# wheel.net
KiCad netlist of a schematic drawn in EAGLE
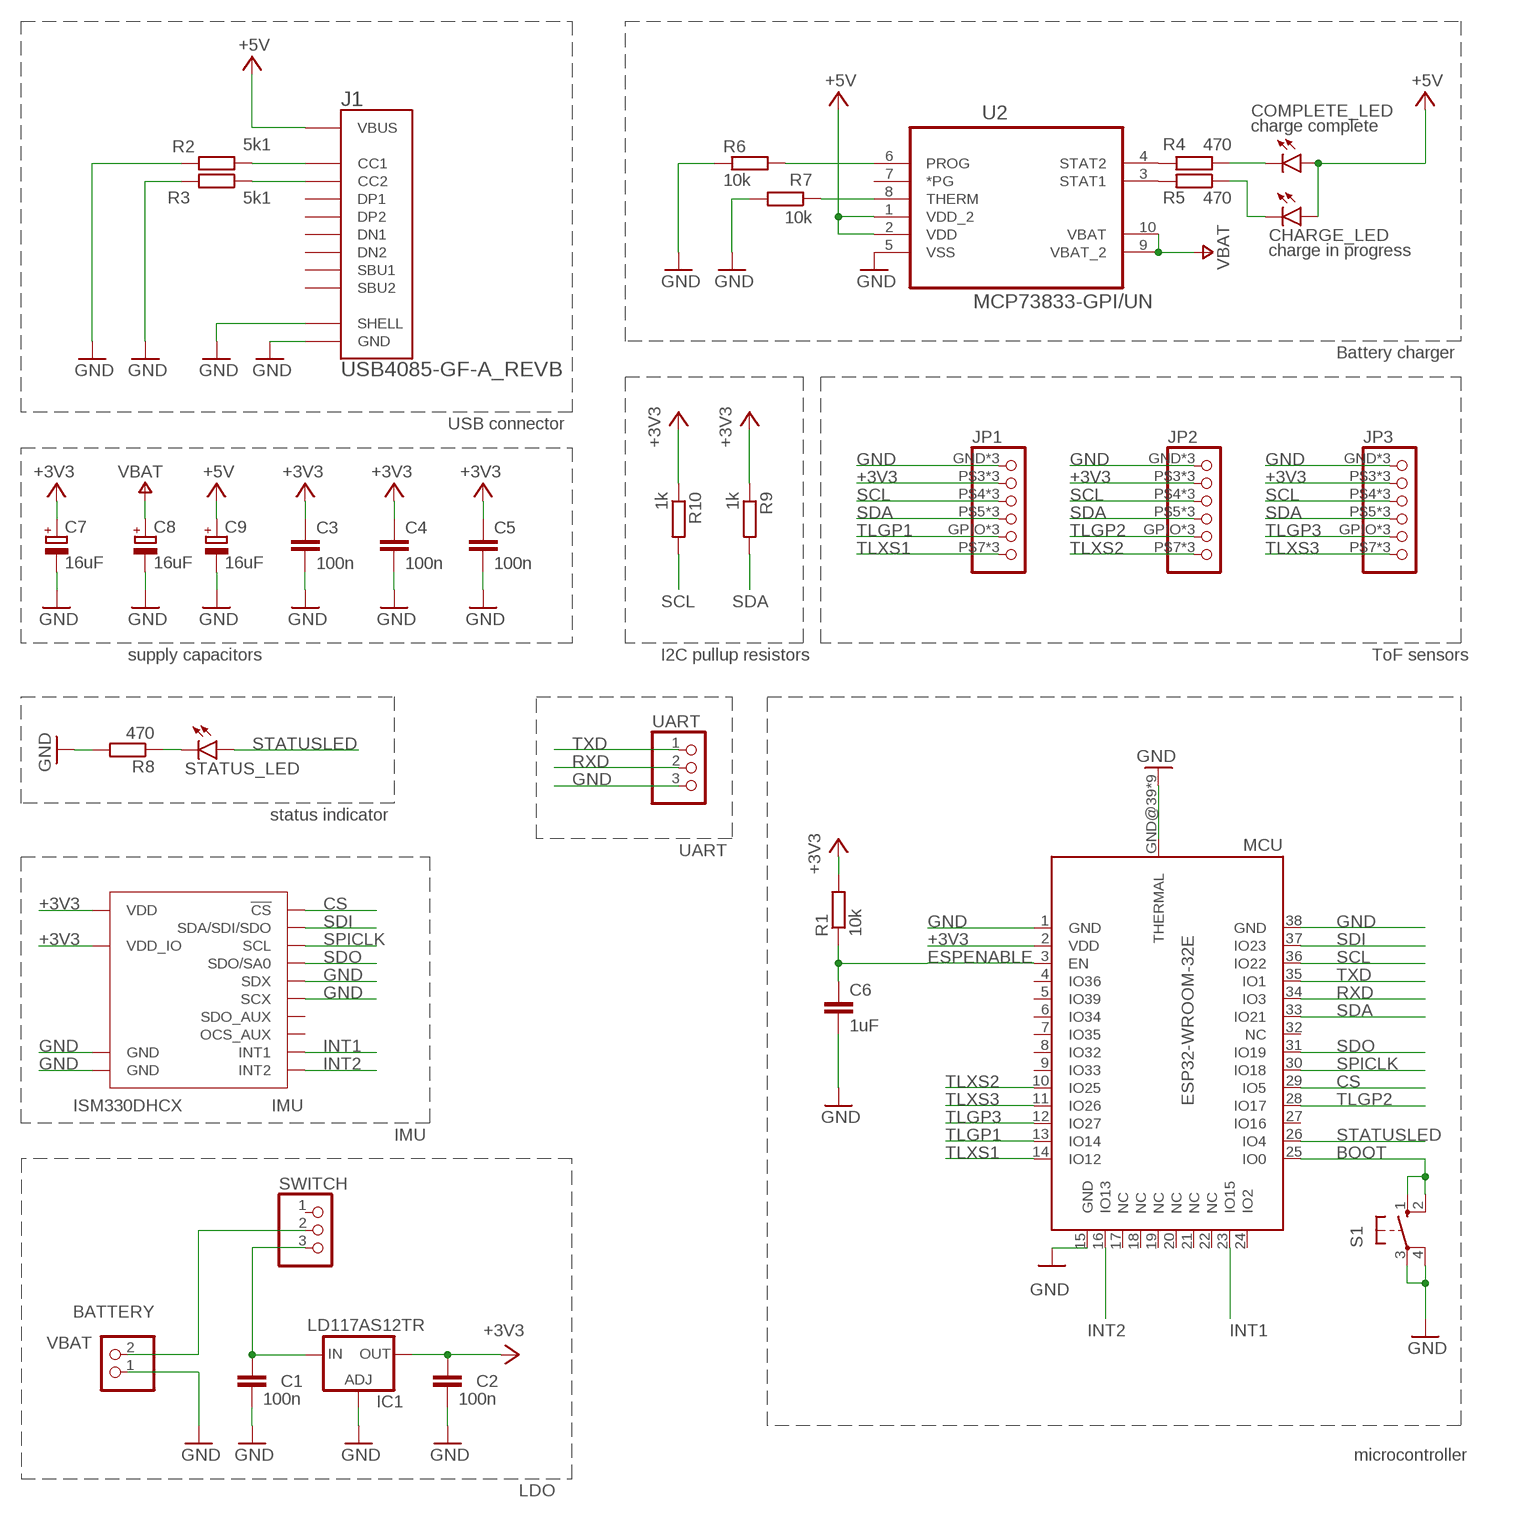
[diagram p0: schematic, sheet 1]

(export (version "E")
  (design (tool "Eeschema 10.0.6"))
  (components
    (comp (ref "BATTERY")
      (value "PINHD-1X2")
      (footprint "eagle-import:1X02")
      (libsource (lib "eagle-import") (part "PINHD-1X2"))
    )
    (comp (ref "C1")
      (value "100n")
      (footprint "eagle-import:C1206")
      (libsource (lib "eagle-import") (part "C-EUC1206"))
    )
    (comp (ref "C2")
      (value "100n")
      (footprint "eagle-import:C1206")
      (libsource (lib "eagle-import") (part "C-EUC1206"))
    )
    (comp (ref "C3")
      (value "100n")
      (footprint "eagle-import:C1206")
      (libsource (lib "eagle-import") (part "C-EUC1206"))
    )
    (comp (ref "C4")
      (value "100n")
      (footprint "eagle-import:C1206")
      (libsource (lib "eagle-import") (part "C-EUC1206"))
    )
    (comp (ref "C5")
      (value "100n")
      (footprint "eagle-import:C1206")
      (libsource (lib "eagle-import") (part "C-EUC1206"))
    )
    (comp (ref "C6")
      (value "1uF")
      (footprint "eagle-import:C1206")
      (libsource (lib "eagle-import") (part "C-EUC1206"))
    )
    (comp (ref "C7")
      (value "16uF")
      (footprint "eagle-import:E2,5-7")
      (libsource (lib "eagle-import") (part "CPOL-EUE2.5-7"))
    )
    (comp (ref "C8")
      (value "16uF")
      (footprint "eagle-import:E2,5-7")
      (libsource (lib "eagle-import") (part "CPOL-EUE2.5-7"))
    )
    (comp (ref "C9")
      (value "16uF")
      (footprint "eagle-import:E2,5-7")
      (libsource (lib "eagle-import") (part "CPOL-EUE2.5-7"))
    )
    (comp (ref "CHARGE_LED")
      (value "charge in progress")
      (footprint "eagle-import:CHIPLED_1206")
      (libsource (lib "eagle-import") (part "LEDCHIPLED_1206"))
    )
    (comp (ref "COMPLETE_LED")
      (value "charge complete")
      (footprint "eagle-import:CHIPLED_1206")
      (libsource (lib "eagle-import") (part "LEDCHIPLED_1206"))
    )
    (comp (ref "IC1")
      (value "LD117AS12TR")
      (footprint "eagle-import:SOT223")
      (libsource (lib "eagle-import") (part "LD117A?S12TR"))
    )
    (comp (ref "IMU")
      (value "ISM330DHCX")
      (footprint "eagle-import:LGA-14L")
      (libsource (lib "eagle-import") (part "ISM330DHCX"))
    )
    (comp (ref "J1")
      (value "USB4085-GF-A_REVB")
      (footprint "eagle-import:GCT_USB4085-GF-A_REVB")
      (fields (field (name "MF") "Global Connector Technology") (field (name "MP") "USB4085-GF-A"))
      (libsource (lib "eagle-import") (part "USB4085-GF-A_REVB"))
    )
    (comp (ref "JP1")
      (value "PINHD-1X6")
      (footprint "eagle-import:1X06")
      (libsource (lib "eagle-import") (part "PINHD-1X6"))
    )
    (comp (ref "JP2")
      (value "PINHD-1X6")
      (footprint "eagle-import:1X06")
      (libsource (lib "eagle-import") (part "PINHD-1X6"))
    )
    (comp (ref "JP3")
      (value "PINHD-1X6")
      (footprint "eagle-import:1X06")
      (libsource (lib "eagle-import") (part "PINHD-1X6"))
    )
    (comp (ref "MCU")
      (value "ESP32-WROOM-32E")
      (footprint "eagle-import:ESP32-WROOM-32E")
      (fields (field (name "MF") "Espressif Systems"))
      (libsource (lib "eagle-import") (part "ESP32-WROOM-32E"))
    )
    (comp (ref "R1")
      (value "10k")
      (footprint "eagle-import:R1206")
      (libsource (lib "eagle-import") (part "R-EU_R1206"))
    )
    (comp (ref "R2")
      (value "5k1")
      (footprint "eagle-import:R1206")
      (libsource (lib "eagle-import") (part "R-EU_R1206"))
    )
    (comp (ref "R3")
      (value "5k1")
      (footprint "eagle-import:R1206")
      (libsource (lib "eagle-import") (part "R-EU_R1206"))
    )
    (comp (ref "R4")
      (value "470")
      (footprint "eagle-import:R1206")
      (libsource (lib "eagle-import") (part "R-EU_R1206"))
    )
    (comp (ref "R5")
      (value "470")
      (footprint "eagle-import:R1206")
      (libsource (lib "eagle-import") (part "R-EU_R1206"))
    )
    (comp (ref "R6")
      (value "10k")
      (footprint "eagle-import:R1206")
      (libsource (lib "eagle-import") (part "R-EU_R1206"))
    )
    (comp (ref "R7")
      (value "10k")
      (footprint "eagle-import:R1206")
      (libsource (lib "eagle-import") (part "R-EU_R1206"))
    )
    (comp (ref "R8")
      (value "470")
      (footprint "eagle-import:R1206")
      (libsource (lib "eagle-import") (part "R-EU_R1206"))
    )
    (comp (ref "R9")
      (value "1k")
      (footprint "eagle-import:R1206")
      (libsource (lib "eagle-import") (part "R-EU_R1206"))
    )
    (comp (ref "R10")
      (value "1k")
      (footprint "eagle-import:R1206")
      (libsource (lib "eagle-import") (part "R-EU_R1206"))
    )
    (comp (ref "S1")
      (value "10-XX")
      (footprint "eagle-import:B3F-10XX")
      (fields (field (name "MPN") "B3F-1000"))
      (libsource (lib "eagle-import") (part "10-XX"))
    )
    (comp (ref "STATUS_LED")
      (value "status")
      (footprint "eagle-import:CHIPLED_1206")
      (libsource (lib "eagle-import") (part "LEDCHIPLED_1206"))
    )
    (comp (ref "SWITCH")
      (value "PINHD-1X3")
      (footprint "eagle-import:1X03")
      (libsource (lib "eagle-import") (part "PINHD-1X3"))
    )
    (comp (ref "U2")
      (value "MCP73833-GPI/UN")
      (footprint "eagle-import:SOP50P490X110-10N")
      (fields (field (name "MF") "Microchip"))
      (libsource (lib "eagle-import") (part "MCP73833-GPI/UN"))
    )
    (comp (ref "UART")
      (value "PINHD-1X3")
      (footprint "eagle-import:1X03")
      (libsource (lib "eagle-import") (part "PINHD-1X3"))
    )
  )
  (nets
    (net (code "1") (name "+3V3") (class "Default")
      (node (ref "C2") (pin "1") (pinfunction "1_1") (pintype "passive"))
      (node (ref "C3") (pin "1") (pinfunction "1_1") (pintype "passive"))
      (node (ref "C4") (pin "1") (pinfunction "1_1") (pintype "passive"))
      (node (ref "C5") (pin "1") (pinfunction "1_1") (pintype "passive"))
      (node (ref "C7") (pin "+") (pinfunction "+_+") (pintype "passive"))
      (node (ref "IC1") (pin "4") (pinfunction "OUT_4") (pintype "passive"))
      (node (ref "IMU") (pin "P5") (pinfunction "VDD_IO_P5") (pintype "power_in"))
      (node (ref "IMU") (pin "P8") (pinfunction "VDD_P8") (pintype "power_in"))
      (node (ref "JP1") (pin "P$3") (pinfunction "2_P$3") (pintype "passive"))
      (node (ref "JP1") (pin "P$8") (pinfunction "2_P$8") (pintype "passive"))
      (node (ref "JP1") (pin "VCC") (pinfunction "2_VCC") (pintype "passive"))
      (node (ref "JP2") (pin "P$3") (pinfunction "2_P$3") (pintype "passive"))
      (node (ref "JP2") (pin "P$8") (pinfunction "2_P$8") (pintype "passive"))
      (node (ref "JP2") (pin "VCC") (pinfunction "2_VCC") (pintype "passive"))
      (node (ref "JP3") (pin "P$3") (pinfunction "2_P$3") (pintype "passive"))
      (node (ref "JP3") (pin "P$8") (pinfunction "2_P$8") (pintype "passive"))
      (node (ref "JP3") (pin "VCC") (pinfunction "2_VCC") (pintype "passive"))
      (node (ref "MCU") (pin "2") (pinfunction "VDD_2") (pintype "bidirectional"))
      (node (ref "R1") (pin "2") (pinfunction "2_2") (pintype "passive"))
      (node (ref "R10") (pin "1") (pinfunction "1_1") (pintype "passive"))
      (node (ref "R9") (pin "1") (pinfunction "1_1") (pintype "passive"))
    )
    (net (code "2") (name "+5V") (class "Default")
      (node (ref "C9") (pin "+") (pinfunction "+_+") (pintype "passive"))
      (node (ref "CHARGE_LED") (pin "A") (pinfunction "A_A") (pintype "passive"))
      (node (ref "COMPLETE_LED") (pin "A") (pinfunction "A_A") (pintype "passive"))
      (node (ref "J1") (pin "A4") (pinfunction "VBUS_A4") (pintype "power_in"))
      (node (ref "J1") (pin "A9") (pinfunction "VBUS_A9") (pintype "power_in"))
      (node (ref "J1") (pin "B4") (pinfunction "VBUS_B4") (pintype "power_in"))
      (node (ref "J1") (pin "B9") (pinfunction "VBUS_B9") (pintype "power_in"))
      (node (ref "U2") (pin "1") (pinfunction "VDD_2_1") (pintype "power_in"))
      (node (ref "U2") (pin "2") (pinfunction "VDD_2") (pintype "power_in"))
    )
    (net (code "3") (name "/BOOT") (class "Default")
      (node (ref "MCU") (pin "25") (pinfunction "IO0_25") (pintype "bidirectional"))
      (node (ref "S1") (pin "1") (pinfunction "S_1") (pintype "passive"))
      (node (ref "S1") (pin "2") (pinfunction "S1_2") (pintype "passive"))
    )
    (net (code "4") (name "/CS") (class "Default")
      (node (ref "IMU") (pin "P12") (pinfunction "~{CS}_P12") (pintype "bidirectional"))
      (node (ref "MCU") (pin "29") (pinfunction "IO5_29") (pintype "bidirectional"))
    )
    (net (code "5") (name "/ESPENABLE") (class "Default")
      (node (ref "C6") (pin "1") (pinfunction "1_1") (pintype "passive"))
      (node (ref "MCU") (pin "3") (pinfunction "EN_3") (pintype "bidirectional"))
      (node (ref "R1") (pin "1") (pinfunction "1_1") (pintype "passive"))
    )
    (net (code "6") (name "/INT1") (class "Default")
      (node (ref "IMU") (pin "P4") (pinfunction "INT1_P4") (pintype "bidirectional"))
      (node (ref "MCU") (pin "23") (pinfunction "IO15_23") (pintype "bidirectional"))
    )
    (net (code "7") (name "/INT2") (class "Default")
      (node (ref "IMU") (pin "P9") (pinfunction "INT2_P9") (pintype "bidirectional"))
      (node (ref "MCU") (pin "16") (pinfunction "IO13_16") (pintype "bidirectional"))
    )
    (net (code "8") (name "/RXD") (class "Default")
      (node (ref "MCU") (pin "34") (pinfunction "IO3_34") (pintype "bidirectional"))
      (node (ref "UART") (pin "2") (pinfunction "2_2") (pintype "passive"))
    )
    (net (code "9") (name "/SCL") (class "Default")
      (node (ref "JP1") (pin "P$4") (pinfunction "3_P$4") (pintype "passive"))
      (node (ref "JP1") (pin "P$9") (pinfunction "3_P$9") (pintype "passive"))
      (node (ref "JP1") (pin "SCL") (pinfunction "3_SCL") (pintype "passive"))
      (node (ref "JP2") (pin "P$4") (pinfunction "3_P$4") (pintype "passive"))
      (node (ref "JP2") (pin "P$9") (pinfunction "3_P$9") (pintype "passive"))
      (node (ref "JP2") (pin "SCL") (pinfunction "3_SCL") (pintype "passive"))
      (node (ref "JP3") (pin "P$4") (pinfunction "3_P$4") (pintype "passive"))
      (node (ref "JP3") (pin "P$9") (pinfunction "3_P$9") (pintype "passive"))
      (node (ref "JP3") (pin "SCL") (pinfunction "3_SCL") (pintype "passive"))
      (node (ref "MCU") (pin "36") (pinfunction "IO22_36") (pintype "bidirectional"))
      (node (ref "R10") (pin "2") (pinfunction "2_2") (pintype "passive"))
    )
    (net (code "10") (name "/SDA") (class "Default")
      (node (ref "JP1") (pin "P$10") (pinfunction "4_P$10") (pintype "passive"))
      (node (ref "JP1") (pin "P$5") (pinfunction "4_P$5") (pintype "passive"))
      (node (ref "JP1") (pin "SDA") (pinfunction "4_SDA") (pintype "passive"))
      (node (ref "JP2") (pin "P$10") (pinfunction "4_P$10") (pintype "passive"))
      (node (ref "JP2") (pin "P$5") (pinfunction "4_P$5") (pintype "passive"))
      (node (ref "JP2") (pin "SDA") (pinfunction "4_SDA") (pintype "passive"))
      (node (ref "JP3") (pin "P$10") (pinfunction "4_P$10") (pintype "passive"))
      (node (ref "JP3") (pin "P$5") (pinfunction "4_P$5") (pintype "passive"))
      (node (ref "JP3") (pin "SDA") (pinfunction "4_SDA") (pintype "passive"))
      (node (ref "MCU") (pin "33") (pinfunction "IO21_33") (pintype "bidirectional"))
      (node (ref "R9") (pin "2") (pinfunction "2_2") (pintype "passive"))
    )
    (net (code "11") (name "/SDI") (class "Default")
      (node (ref "IMU") (pin "P14") (pinfunction "SDA/SDI/SDO_P14") (pintype "bidirectional"))
      (node (ref "MCU") (pin "37") (pinfunction "IO23_37") (pintype "bidirectional"))
    )
    (net (code "12") (name "/SDO") (class "Default")
      (node (ref "IMU") (pin "P1") (pinfunction "SDO/SA0_P1") (pintype "bidirectional"))
      (node (ref "MCU") (pin "31") (pinfunction "IO19_31") (pintype "bidirectional"))
    )
    (net (code "13") (name "/SPICLK") (class "Default")
      (node (ref "IMU") (pin "P13") (pinfunction "SCL_P13") (pintype "bidirectional"))
      (node (ref "MCU") (pin "30") (pinfunction "IO18_30") (pintype "bidirectional"))
    )
    (net (code "14") (name "/STATUSLED") (class "Default")
      (node (ref "MCU") (pin "26") (pinfunction "IO4_26") (pintype "bidirectional"))
      (node (ref "STATUS_LED") (pin "A") (pinfunction "A_A") (pintype "passive"))
    )
    (net (code "15") (name "/TLGP1") (class "Default")
      (node (ref "JP1") (pin "GPIO") (pinfunction "5_GPIO") (pintype "passive"))
      (node (ref "JP1") (pin "P$11") (pinfunction "5_P$11") (pintype "passive"))
      (node (ref "JP1") (pin "P$6") (pinfunction "5_P$6") (pintype "passive"))
      (node (ref "MCU") (pin "13") (pinfunction "IO14_13") (pintype "bidirectional"))
    )
    (net (code "16") (name "/TLGP2") (class "Default")
      (node (ref "JP2") (pin "GPIO") (pinfunction "5_GPIO") (pintype "passive"))
      (node (ref "JP2") (pin "P$11") (pinfunction "5_P$11") (pintype "passive"))
      (node (ref "JP2") (pin "P$6") (pinfunction "5_P$6") (pintype "passive"))
      (node (ref "MCU") (pin "28") (pinfunction "IO17_28") (pintype "bidirectional"))
    )
    (net (code "17") (name "/TLGP3") (class "Default")
      (node (ref "JP3") (pin "GPIO") (pinfunction "5_GPIO") (pintype "passive"))
      (node (ref "JP3") (pin "P$11") (pinfunction "5_P$11") (pintype "passive"))
      (node (ref "JP3") (pin "P$6") (pinfunction "5_P$6") (pintype "passive"))
      (node (ref "MCU") (pin "12") (pinfunction "IO27_12") (pintype "bidirectional"))
    )
    (net (code "18") (name "/TLXS1") (class "Default")
      (node (ref "JP1") (pin "P$12") (pinfunction "6_P$12") (pintype "passive"))
      (node (ref "JP1") (pin "P$7") (pinfunction "6_P$7") (pintype "passive"))
      (node (ref "JP1") (pin "XSHUT") (pinfunction "6_XSHUT") (pintype "passive"))
      (node (ref "MCU") (pin "14") (pinfunction "IO12_14") (pintype "bidirectional"))
    )
    (net (code "19") (name "/TLXS2") (class "Default")
      (node (ref "JP2") (pin "P$12") (pinfunction "6_P$12") (pintype "passive"))
      (node (ref "JP2") (pin "P$7") (pinfunction "6_P$7") (pintype "passive"))
      (node (ref "JP2") (pin "XSHUT") (pinfunction "6_XSHUT") (pintype "passive"))
      (node (ref "MCU") (pin "10") (pinfunction "IO25_10") (pintype "bidirectional"))
    )
    (net (code "20") (name "/TLXS3") (class "Default")
      (node (ref "JP3") (pin "P$12") (pinfunction "6_P$12") (pintype "passive"))
      (node (ref "JP3") (pin "P$7") (pinfunction "6_P$7") (pintype "passive"))
      (node (ref "JP3") (pin "XSHUT") (pinfunction "6_XSHUT") (pintype "passive"))
      (node (ref "MCU") (pin "11") (pinfunction "IO26_11") (pintype "bidirectional"))
    )
    (net (code "21") (name "/TXD") (class "Default")
      (node (ref "MCU") (pin "35") (pinfunction "IO1_35") (pintype "bidirectional"))
      (node (ref "UART") (pin "1") (pinfunction "1_1") (pintype "passive"))
    )
    (net (code "22") (name "GND") (class "Default")
      (node (ref "BATTERY") (pin "1") (pinfunction "1_1") (pintype "passive"))
      (node (ref "C1") (pin "2") (pinfunction "2_2") (pintype "passive"))
      (node (ref "C2") (pin "2") (pinfunction "2_2") (pintype "passive"))
      (node (ref "C3") (pin "2") (pinfunction "2_2") (pintype "passive"))
      (node (ref "C4") (pin "2") (pinfunction "2_2") (pintype "passive"))
      (node (ref "C5") (pin "2") (pinfunction "2_2") (pintype "passive"))
      (node (ref "C6") (pin "2") (pinfunction "2_2") (pintype "passive"))
      (node (ref "C7") (pin "-") (pinfunction "-_-") (pintype "passive"))
      (node (ref "C8") (pin "-") (pinfunction "-_-") (pintype "passive"))
      (node (ref "C9") (pin "-") (pinfunction "-_-") (pintype "passive"))
      (node (ref "IC1") (pin "1") (pinfunction "ADJ_1") (pintype "input"))
      (node (ref "IMU") (pin "P2") (pinfunction "SDX_P2") (pintype "bidirectional"))
      (node (ref "IMU") (pin "P3") (pinfunction "SCX_P3") (pintype "bidirectional"))
      (node (ref "IMU") (pin "P6") (pinfunction "GND_P6") (pintype "power_in"))
      (node (ref "IMU") (pin "P7") (pinfunction "GND_P7") (pintype "power_in"))
      (node (ref "J1") (pin "A1") (pinfunction "GND_A1") (pintype "power_in"))
      (node (ref "J1") (pin "A12") (pinfunction "GND_A12") (pintype "power_in"))
      (node (ref "J1") (pin "B1") (pinfunction "GND_B1") (pintype "power_in"))
      (node (ref "J1") (pin "B12") (pinfunction "GND_B12") (pintype "power_in"))
      (node (ref "J1") (pin "S1") (pinfunction "SHELL_S1") (pintype "passive"))
      (node (ref "J1") (pin "S2") (pinfunction "SHELL_S2") (pintype "passive"))
      (node (ref "J1") (pin "S3") (pinfunction "SHELL_S3") (pintype "passive"))
      (node (ref "J1") (pin "S4") (pinfunction "SHELL_S4") (pintype "passive"))
      (node (ref "JP1") (pin "GND") (pinfunction "1_GND") (pintype "passive"))
      (node (ref "JP1") (pin "P$1") (pinfunction "1_P$1") (pintype "passive"))
      (node (ref "JP1") (pin "P$2") (pinfunction "1_P$2") (pintype "passive"))
      (node (ref "JP2") (pin "GND") (pinfunction "1_GND") (pintype "passive"))
      (node (ref "JP2") (pin "P$1") (pinfunction "1_P$1") (pintype "passive"))
      (node (ref "JP2") (pin "P$2") (pinfunction "1_P$2") (pintype "passive"))
      (node (ref "JP3") (pin "GND") (pinfunction "1_GND") (pintype "passive"))
      (node (ref "JP3") (pin "P$1") (pinfunction "1_P$1") (pintype "passive"))
      (node (ref "JP3") (pin "P$2") (pinfunction "1_P$2") (pintype "passive"))
      (node (ref "MCU") (pin "1") (pinfunction "GND_1") (pintype "bidirectional"))
      (node (ref "MCU") (pin "15") (pinfunction "GND_15") (pintype "bidirectional"))
      (node (ref "MCU") (pin "38") (pinfunction "GND_38") (pintype "bidirectional"))
      (node (ref "MCU") (pin "GND@39") (pinfunction "THERMAL_GND@39") (pintype "bidirectional"))
      (node (ref "MCU") (pin "GND@40") (pinfunction "THERMAL_GND@40") (pintype "bidirectional"))
      (node (ref "MCU") (pin "GND@41") (pinfunction "THERMAL_GND@41") (pintype "bidirectional"))
      (node (ref "MCU") (pin "GND@42") (pinfunction "THERMAL_GND@42") (pintype "bidirectional"))
      (node (ref "MCU") (pin "GND@43") (pinfunction "THERMAL_GND@43") (pintype "bidirectional"))
      (node (ref "MCU") (pin "GND@44") (pinfunction "THERMAL_GND@44") (pintype "bidirectional"))
      (node (ref "MCU") (pin "GND@45") (pinfunction "THERMAL_GND@45") (pintype "bidirectional"))
      (node (ref "MCU") (pin "GND@46") (pinfunction "THERMAL_GND@46") (pintype "bidirectional"))
      (node (ref "MCU") (pin "GND@47") (pinfunction "THERMAL_GND@47") (pintype "bidirectional"))
      (node (ref "R2") (pin "2") (pinfunction "2_2") (pintype "passive"))
      (node (ref "R3") (pin "2") (pinfunction "2_2") (pintype "passive"))
      (node (ref "R6") (pin "2") (pinfunction "2_2") (pintype "passive"))
      (node (ref "R7") (pin "2") (pinfunction "2_2") (pintype "passive"))
      (node (ref "R8") (pin "2") (pinfunction "2_2") (pintype "passive"))
      (node (ref "S1") (pin "3") (pinfunction "P_3") (pintype "passive"))
      (node (ref "S1") (pin "4") (pinfunction "P1_4") (pintype "passive"))
      (node (ref "U2") (pin "5") (pinfunction "VSS_5") (pintype "passive"))
      (node (ref "UART") (pin "3") (pinfunction "3_3") (pintype "passive"))
    )
    (net (code "23") (name "Net-(CHARGE_LED-PadC)") (class "Default")
      (node (ref "CHARGE_LED") (pin "C") (pinfunction "C_C") (pintype "passive"))
      (node (ref "R5") (pin "1") (pinfunction "1_1") (pintype "passive"))
    )
    (net (code "24") (name "Net-(COMPLETE_LED-PadC)") (class "Default")
      (node (ref "COMPLETE_LED") (pin "C") (pinfunction "C_C") (pintype "passive"))
      (node (ref "R4") (pin "1") (pinfunction "1_1") (pintype "passive"))
    )
    (net (code "25") (name "Net-(IC1-IN)") (class "Default")
      (node (ref "C1") (pin "1") (pinfunction "1_1") (pintype "passive"))
      (node (ref "IC1") (pin "3") (pinfunction "IN_3") (pintype "input"))
      (node (ref "SWITCH") (pin "3") (pinfunction "3_3") (pintype "passive"))
    )
    (net (code "26") (name "Net-(J1-CC1)") (class "Default")
      (node (ref "J1") (pin "A5") (pinfunction "CC1_A5") (pintype "bidirectional"))
      (node (ref "R2") (pin "1") (pinfunction "1_1") (pintype "passive"))
    )
    (net (code "27") (name "Net-(J1-CC2)") (class "Default")
      (node (ref "J1") (pin "B5") (pinfunction "CC2_B5") (pintype "bidirectional"))
      (node (ref "R3") (pin "1") (pinfunction "1_1") (pintype "passive"))
    )
    (net (code "28") (name "Net-(R8-Pad1)") (class "Default")
      (node (ref "R8") (pin "1") (pinfunction "1_1") (pintype "passive"))
      (node (ref "STATUS_LED") (pin "C") (pinfunction "C_C") (pintype "passive"))
    )
    (net (code "29") (name "Net-(U2-PROG)") (class "Default")
      (node (ref "R6") (pin "1") (pinfunction "1_1") (pintype "passive"))
      (node (ref "U2") (pin "6") (pinfunction "PROG_6") (pintype "input"))
    )
    (net (code "30") (name "Net-(U2-STAT1)") (class "Default")
      (node (ref "R5") (pin "2") (pinfunction "2_2") (pintype "passive"))
      (node (ref "U2") (pin "3") (pinfunction "STAT1_3") (pintype "output"))
    )
    (net (code "31") (name "Net-(U2-STAT2)") (class "Default")
      (node (ref "R4") (pin "2") (pinfunction "2_2") (pintype "passive"))
      (node (ref "U2") (pin "4") (pinfunction "STAT2_4") (pintype "output"))
    )
    (net (code "32") (name "Net-(U2-THERM)") (class "Default")
      (node (ref "R7") (pin "1") (pinfunction "1_1") (pintype "passive"))
      (node (ref "U2") (pin "8") (pinfunction "THERM_8") (pintype "input"))
    )
    (net (code "33") (name "VBAT") (class "Default")
      (node (ref "BATTERY") (pin "2") (pinfunction "2_2") (pintype "passive"))
      (node (ref "C8") (pin "+") (pinfunction "+_+") (pintype "passive"))
      (node (ref "SWITCH") (pin "2") (pinfunction "2_2") (pintype "passive"))
      (node (ref "U2") (pin "10") (pinfunction "VBAT_10") (pintype "output"))
      (node (ref "U2") (pin "9") (pinfunction "VBAT_2_9") (pintype "output"))
    )
    (net (code "34") (name "unconnected-(IMU-OCS_AUX-PadP10)") (class "Default")
      (node (ref "IMU") (pin "P10") (pinfunction "OCS_AUX_P10") (pintype "bidirectional"))
    )
    (net (code "35") (name "unconnected-(IMU-SDO_AUX-PadP11)") (class "Default")
      (node (ref "IMU") (pin "P11") (pinfunction "SDO_AUX_P11") (pintype "bidirectional"))
    )
    (net (code "36") (name "unconnected-(J1-DN1-PadA7)") (class "Default")
      (node (ref "J1") (pin "A7") (pinfunction "DN1_A7") (pintype "bidirectional"))
    )
    (net (code "37") (name "unconnected-(J1-DN2-PadB7)") (class "Default")
      (node (ref "J1") (pin "B7") (pinfunction "DN2_B7") (pintype "bidirectional"))
    )
    (net (code "38") (name "unconnected-(J1-DP1-PadA6)") (class "Default")
      (node (ref "J1") (pin "A6") (pinfunction "DP1_A6") (pintype "bidirectional"))
    )
    (net (code "39") (name "unconnected-(J1-DP2-PadB6)") (class "Default")
      (node (ref "J1") (pin "B6") (pinfunction "DP2_B6") (pintype "bidirectional"))
    )
    (net (code "40") (name "unconnected-(J1-SBU1-PadA8)") (class "Default")
      (node (ref "J1") (pin "A8") (pinfunction "SBU1_A8") (pintype "bidirectional"))
    )
    (net (code "41") (name "unconnected-(J1-SBU2-PadB8)") (class "Default")
      (node (ref "J1") (pin "B8") (pinfunction "SBU2_B8") (pintype "bidirectional"))
    )
    (net (code "42") (name "unconnected-(MCU-IO2-Pad24)") (class "Default")
      (node (ref "MCU") (pin "24") (pinfunction "IO2_24") (pintype "bidirectional"))
    )
    (net (code "43") (name "unconnected-(MCU-IO16-Pad27)") (class "Default")
      (node (ref "MCU") (pin "27") (pinfunction "IO16_27") (pintype "bidirectional"))
    )
    (net (code "44") (name "unconnected-(MCU-IO32-Pad8)") (class "Default")
      (node (ref "MCU") (pin "8") (pinfunction "IO32_8") (pintype "bidirectional"))
    )
    (net (code "45") (name "unconnected-(MCU-IO33-Pad9)") (class "Default")
      (node (ref "MCU") (pin "9") (pinfunction "IO33_9") (pintype "bidirectional"))
    )
    (net (code "46") (name "unconnected-(MCU-IO34-Pad6)") (class "Default")
      (node (ref "MCU") (pin "6") (pinfunction "IO34_6") (pintype "bidirectional"))
    )
    (net (code "47") (name "unconnected-(MCU-IO35-Pad7)") (class "Default")
      (node (ref "MCU") (pin "7") (pinfunction "IO35_7") (pintype "bidirectional"))
    )
    (net (code "48") (name "unconnected-(MCU-IO36-Pad4)") (class "Default")
      (node (ref "MCU") (pin "4") (pinfunction "IO36_4") (pintype "bidirectional"))
    )
    (net (code "49") (name "unconnected-(MCU-IO39-Pad5)") (class "Default")
      (node (ref "MCU") (pin "5") (pinfunction "IO39_5") (pintype "bidirectional"))
    )
    (net (code "50") (name "unconnected-(MCU-NC-Pad17)") (class "Default")
      (node (ref "MCU") (pin "17") (pinfunction "NC_17") (pintype "bidirectional"))
    )
    (net (code "51") (name "unconnected-(MCU-NC-Pad18)") (class "Default")
      (node (ref "MCU") (pin "18") (pinfunction "NC_18") (pintype "bidirectional"))
    )
    (net (code "52") (name "unconnected-(MCU-NC-Pad19)") (class "Default")
      (node (ref "MCU") (pin "19") (pinfunction "NC_19") (pintype "bidirectional"))
    )
    (net (code "53") (name "unconnected-(MCU-NC-Pad20)") (class "Default")
      (node (ref "MCU") (pin "20") (pinfunction "NC_20") (pintype "bidirectional"))
    )
    (net (code "54") (name "unconnected-(MCU-NC-Pad21)") (class "Default")
      (node (ref "MCU") (pin "21") (pinfunction "NC_21") (pintype "bidirectional"))
    )
    (net (code "55") (name "unconnected-(MCU-NC-Pad22)") (class "Default")
      (node (ref "MCU") (pin "22") (pinfunction "NC_22") (pintype "bidirectional"))
    )
    (net (code "56") (name "unconnected-(MCU-NC-Pad32)") (class "Default")
      (node (ref "MCU") (pin "32") (pinfunction "NC_32") (pintype "bidirectional"))
    )
    (net (code "57") (name "unconnected-(SWITCH-Pad1)") (class "Default")
      (node (ref "SWITCH") (pin "1") (pinfunction "1_1") (pintype "passive"))
    )
    (net (code "58") (name "unconnected-(U2-*PG-Pad7)") (class "Default")
      (node (ref "U2") (pin "7") (pinfunction "*PG_7") (pintype "input"))
    )
  )
)
